# SCH_FINAL-Kickbots-joystick-2026-06-17.net
KiCad netlist of a schematic drawn in EasyEDA
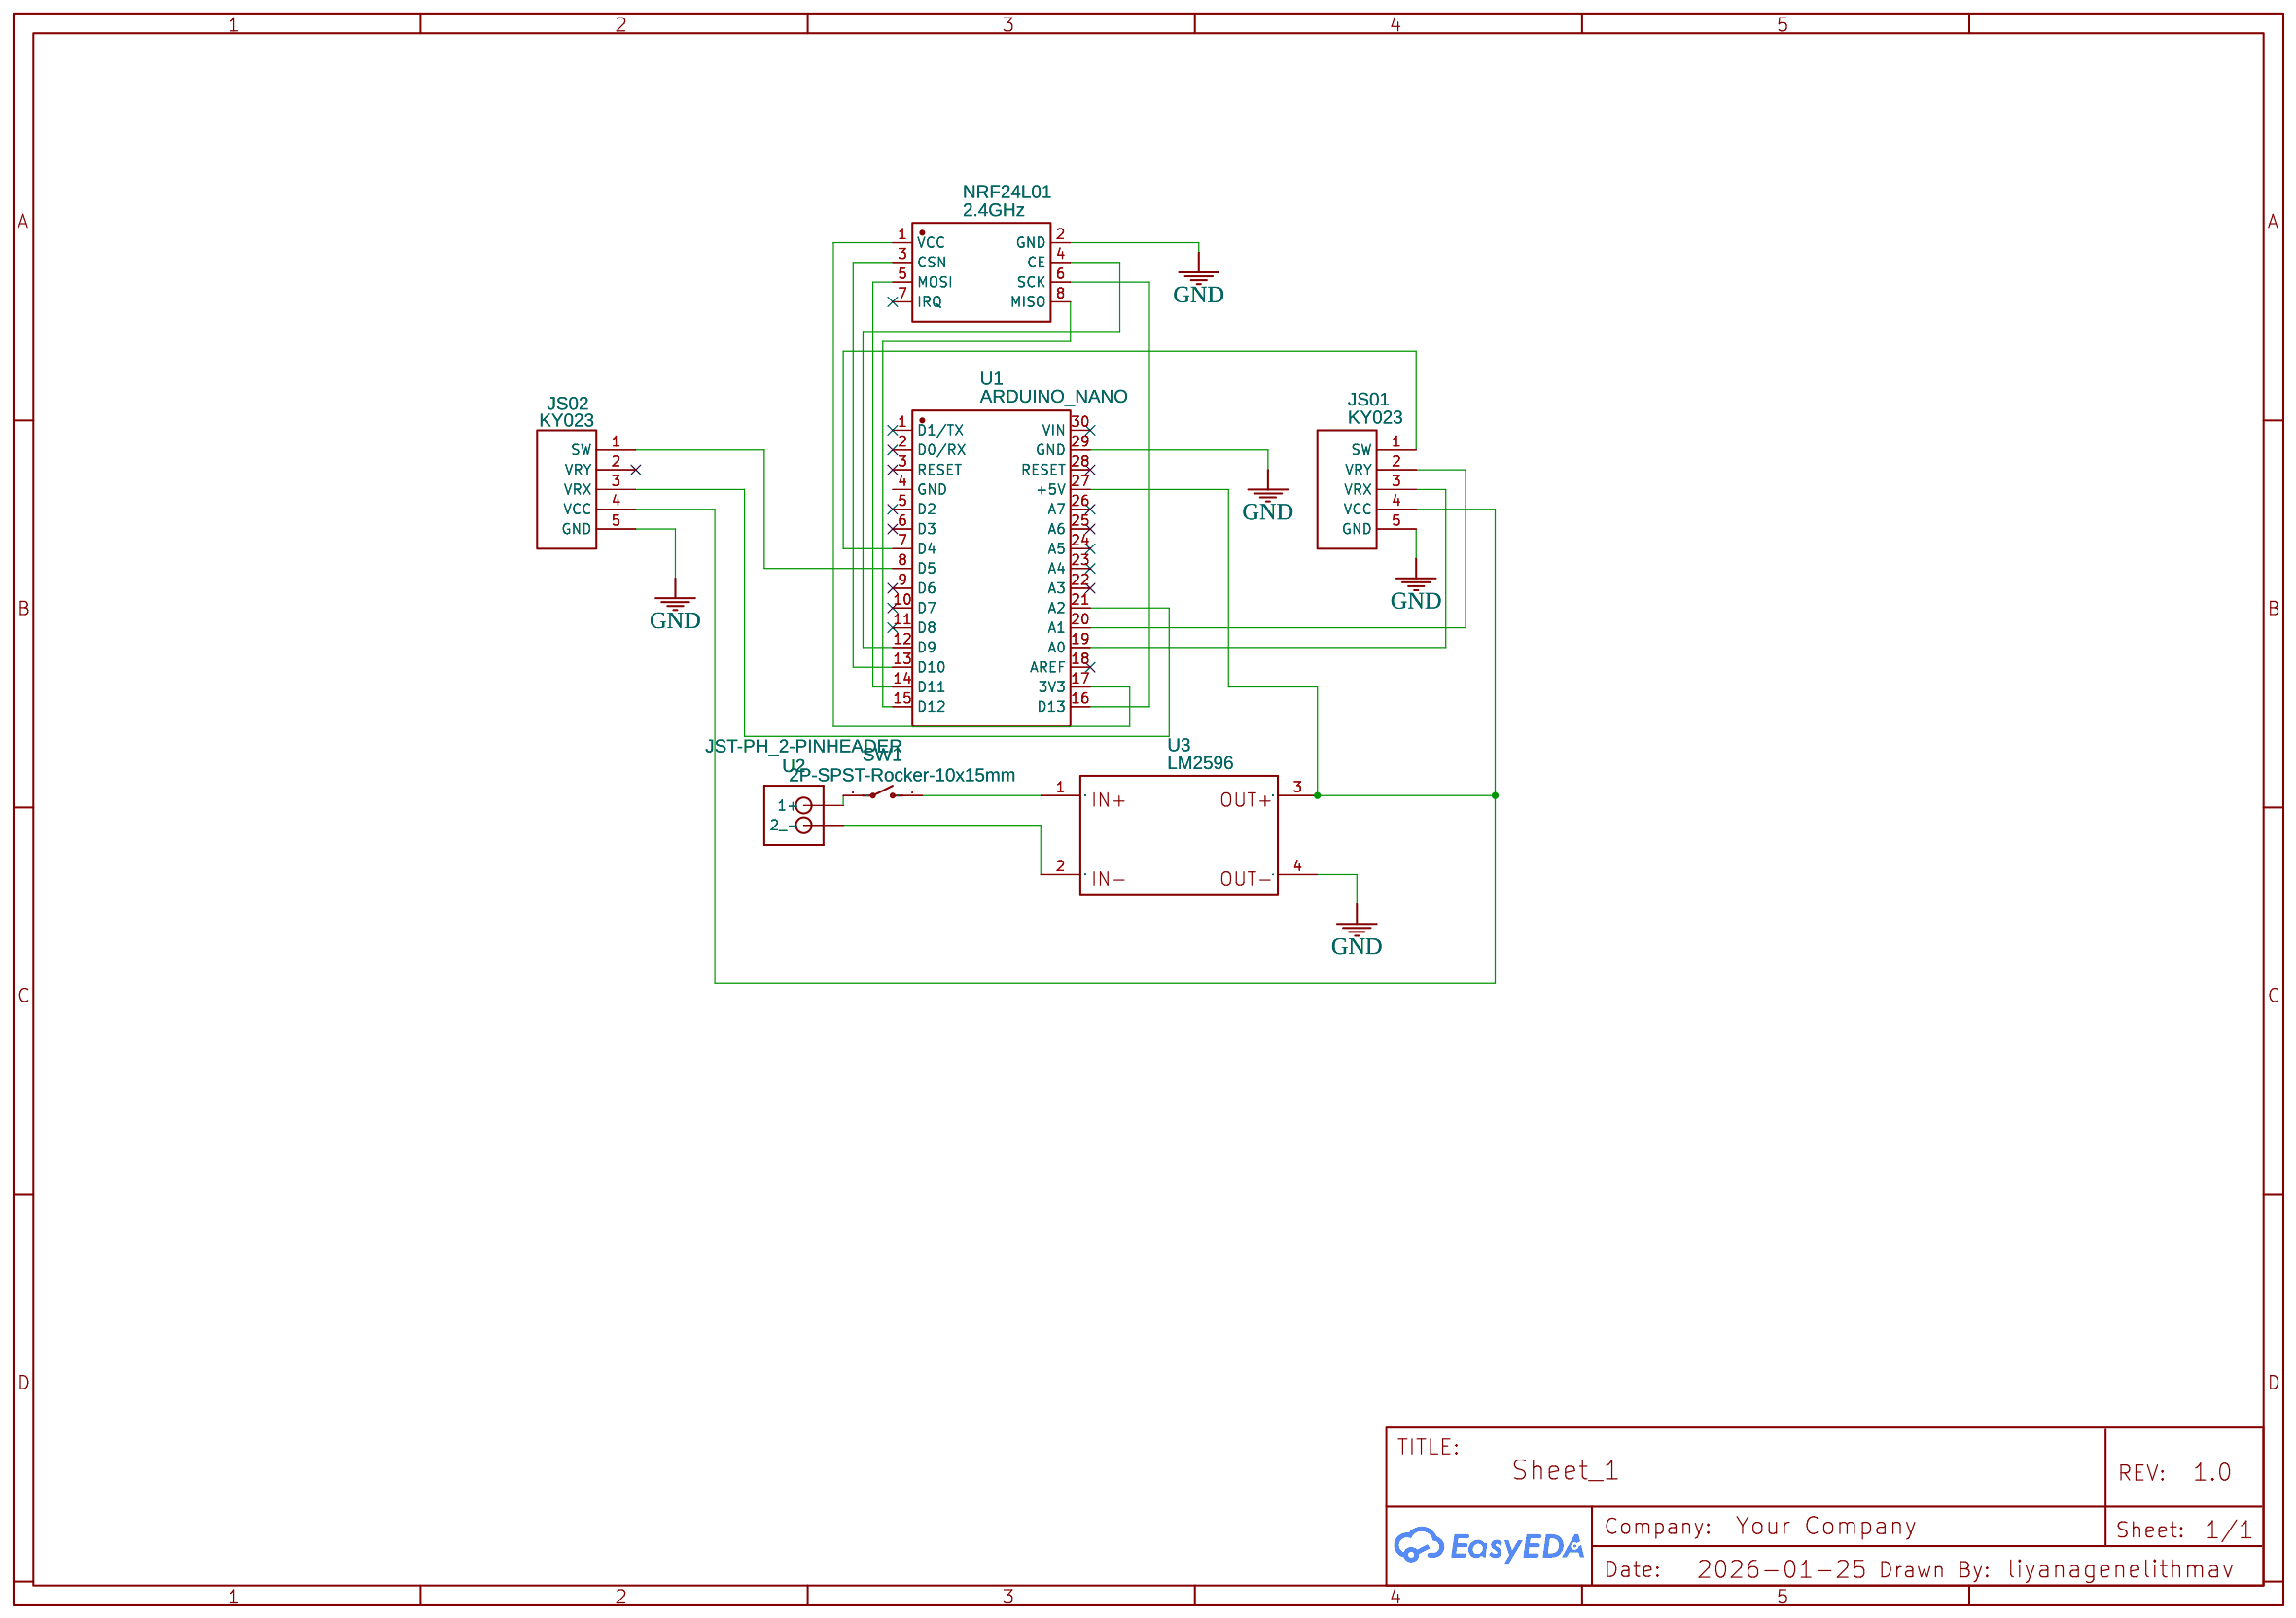
[diagram p0: schematic sheet]

(export (version "E")
  (design (tool "Eeschema 10.0.6"))
  (components
    (comp (ref "JS01") (value "KY023") (libsource (lib "") (part "KY023")))
    (comp (ref "JS02") (value "KY023") (libsource (lib "") (part "KY023")))
    (comp (ref "NRF24L01")
      (value "2.4GHz")
      (fields (field (name "Manufacturer Part") "NF-04") (field (name "Manufacturer") "Ai-Thinker(安信可)"))
      (libsource (lib "") (part "NRF24L01"))
    )
    (comp (ref "SW1")
      (value "2P-SPST-Rocker-10x15mm")
      (fields (field (name "Manufacturer Part") "KCD1-11-1.5x1cm"))
      (libsource (lib "") (part "SWITCH-2P-SPST-Rocker-10x15mm"))
    )
    (comp (ref "U1") (value "ARDUINO_NANO") (libsource (lib "") (part "ARDUINO_NANO")))
    (comp (ref "U2") (value "JST-PH_2-PINHEADER") (libsource (lib "") (part "JST-PH_2-PIN_HEADER")))
    (comp (ref "U3") (value "LM2596") (libsource (lib "") (part "LM2596")))
  )
  (nets
    (net (code "1") (name "GND") (class "Default")
      (node (ref "JS01") (pin "5") (pinfunction "GND_5") (pintype "unspecified"))
      (node (ref "JS02") (pin "5") (pinfunction "GND_5") (pintype "unspecified"))
      (node (ref "NRF24L01") (pin "2") (pinfunction "GND_2") (pintype "unspecified"))
      (node (ref "U1") (pin "29") (pinfunction "GND_29") (pintype "unspecified"))
      (node (ref "U3") (pin "4") (pinfunction "4_4") (pintype "unspecified"))
    )
    (net (code "2") (name "Net-(JS01-SW)") (class "Default")
      (node (ref "JS01") (pin "1") (pinfunction "SW_1") (pintype "unspecified"))
      (node (ref "U1") (pin "7") (pinfunction "D4_7") (pintype "unspecified"))
    )
    (net (code "3") (name "Net-(JS01-VCC)") (class "Default")
      (node (ref "JS01") (pin "4") (pinfunction "VCC_4") (pintype "unspecified"))
      (node (ref "JS02") (pin "4") (pinfunction "VCC_4") (pintype "unspecified"))
      (node (ref "U1") (pin "27") (pinfunction "+5V_27") (pintype "unspecified"))
      (node (ref "U3") (pin "3") (pinfunction "3_3") (pintype "unspecified"))
    )
    (net (code "4") (name "Net-(JS01-VRX)") (class "Default")
      (node (ref "JS01") (pin "3") (pinfunction "VRX_3") (pintype "unspecified"))
      (node (ref "U1") (pin "19") (pinfunction "A0_19") (pintype "unspecified"))
    )
    (net (code "5") (name "Net-(JS01-VRY)") (class "Default")
      (node (ref "JS01") (pin "2") (pinfunction "VRY_2") (pintype "unspecified"))
      (node (ref "U1") (pin "20") (pinfunction "A1_20") (pintype "unspecified"))
    )
    (net (code "6") (name "Net-(JS02-SW)") (class "Default")
      (node (ref "JS02") (pin "1") (pinfunction "SW_1") (pintype "unspecified"))
      (node (ref "U1") (pin "8") (pinfunction "D5_8") (pintype "unspecified"))
    )
    (net (code "7") (name "Net-(JS02-VRX)") (class "Default")
      (node (ref "JS02") (pin "3") (pinfunction "VRX_3") (pintype "unspecified"))
      (node (ref "U1") (pin "21") (pinfunction "A2_21") (pintype "unspecified"))
    )
    (net (code "8") (name "Net-(NRF24L01-CE)") (class "Default")
      (node (ref "NRF24L01") (pin "4") (pinfunction "CE_4") (pintype "unspecified"))
      (node (ref "U1") (pin "12") (pinfunction "D9_12") (pintype "unspecified"))
    )
    (net (code "9") (name "Net-(NRF24L01-CSN)") (class "Default")
      (node (ref "NRF24L01") (pin "3") (pinfunction "CSN_3") (pintype "unspecified"))
      (node (ref "U1") (pin "13") (pinfunction "D10_13") (pintype "unspecified"))
    )
    (net (code "10") (name "Net-(NRF24L01-MISO)") (class "Default")
      (node (ref "NRF24L01") (pin "8") (pinfunction "MISO_8") (pintype "unspecified"))
      (node (ref "U1") (pin "15") (pinfunction "D12_15") (pintype "unspecified"))
    )
    (net (code "11") (name "Net-(NRF24L01-MOSI)") (class "Default")
      (node (ref "NRF24L01") (pin "5") (pinfunction "MOSI_5") (pintype "unspecified"))
      (node (ref "U1") (pin "14") (pinfunction "D11_14") (pintype "unspecified"))
    )
    (net (code "12") (name "Net-(NRF24L01-SCK)") (class "Default")
      (node (ref "NRF24L01") (pin "6") (pinfunction "SCK_6") (pintype "unspecified"))
      (node (ref "U1") (pin "16") (pinfunction "D13_16") (pintype "unspecified"))
    )
    (net (code "13") (name "Net-(NRF24L01-VCC)") (class "Default")
      (node (ref "NRF24L01") (pin "1") (pinfunction "VCC_1") (pintype "unspecified"))
      (node (ref "U1") (pin "17") (pinfunction "3V3_17") (pintype "unspecified"))
    )
    (net (code "14") (name "Net-(SW1-O)") (class "Default")
      (node (ref "SW1") (pin "1") (pinfunction "O_1") (pintype "unspecified"))
      (node (ref "U3") (pin "1") (pinfunction "1_1") (pintype "unspecified"))
    )
    (net (code "15") (name "Net-(SW1-P)") (class "Default")
      (node (ref "SW1") (pin "2") (pinfunction "P_2") (pintype "unspecified"))
      (node (ref "U2") (pin "P1") (pinfunction "1+_P1") (pintype "unspecified"))
    )
    (net (code "16") (name "Net-(U2-2_-)") (class "Default")
      (node (ref "U2") (pin "P2") (pinfunction "2_-_P2") (pintype "unspecified"))
      (node (ref "U3") (pin "2") (pinfunction "2_2") (pintype "unspecified"))
    )
    (net (code "17") (name "unconnected-(JS02-VRY-Pad2)") (class "Default")
      (node (ref "JS02") (pin "2") (pinfunction "VRY_2") (pintype "unspecified+no_connect"))
    )
    (net (code "18") (name "unconnected-(NRF24L01-IRQ-Pad7)") (class "Default")
      (node (ref "NRF24L01") (pin "7") (pinfunction "IRQ_7") (pintype "unspecified+no_connect"))
    )
    (net (code "19") (name "unconnected-(U1-A3-Pad22)") (class "Default")
      (node (ref "U1") (pin "22") (pinfunction "A3_22") (pintype "unspecified+no_connect"))
    )
    (net (code "20") (name "unconnected-(U1-A4-Pad23)") (class "Default")
      (node (ref "U1") (pin "23") (pinfunction "A4_23") (pintype "unspecified+no_connect"))
    )
    (net (code "21") (name "unconnected-(U1-A5-Pad24)") (class "Default")
      (node (ref "U1") (pin "24") (pinfunction "A5_24") (pintype "unspecified+no_connect"))
    )
    (net (code "22") (name "unconnected-(U1-A6-Pad25)") (class "Default")
      (node (ref "U1") (pin "25") (pinfunction "A6_25") (pintype "unspecified+no_connect"))
    )
    (net (code "23") (name "unconnected-(U1-A7-Pad26)") (class "Default")
      (node (ref "U1") (pin "26") (pinfunction "A7_26") (pintype "unspecified+no_connect"))
    )
    (net (code "24") (name "unconnected-(U1-AREF-Pad18)") (class "Default")
      (node (ref "U1") (pin "18") (pinfunction "AREF_18") (pintype "unspecified+no_connect"))
    )
    (net (code "25") (name "unconnected-(U1-D0{slash}RX-Pad2)") (class "Default")
      (node (ref "U1") (pin "2") (pinfunction "D0/RX_2") (pintype "unspecified+no_connect"))
    )
    (net (code "26") (name "unconnected-(U1-D1{slash}TX-Pad1)") (class "Default")
      (node (ref "U1") (pin "1") (pinfunction "D1/TX_1") (pintype "unspecified+no_connect"))
    )
    (net (code "27") (name "unconnected-(U1-D2-Pad5)") (class "Default")
      (node (ref "U1") (pin "5") (pinfunction "D2_5") (pintype "unspecified+no_connect"))
    )
    (net (code "28") (name "unconnected-(U1-D3-Pad6)") (class "Default")
      (node (ref "U1") (pin "6") (pinfunction "D3_6") (pintype "unspecified+no_connect"))
    )
    (net (code "29") (name "unconnected-(U1-D6-Pad9)") (class "Default")
      (node (ref "U1") (pin "9") (pinfunction "D6_9") (pintype "unspecified+no_connect"))
    )
    (net (code "30") (name "unconnected-(U1-D7-Pad10)") (class "Default")
      (node (ref "U1") (pin "10") (pinfunction "D7_10") (pintype "unspecified+no_connect"))
    )
    (net (code "31") (name "unconnected-(U1-D8-Pad11)") (class "Default")
      (node (ref "U1") (pin "11") (pinfunction "D8_11") (pintype "unspecified+no_connect"))
    )
    (net (code "32") (name "unconnected-(U1-GND-Pad4)") (class "Default")
      (node (ref "U1") (pin "4") (pinfunction "GND_4") (pintype "unspecified"))
    )
    (net (code "33") (name "unconnected-(U1-RESET-Pad3)") (class "Default")
      (node (ref "U1") (pin "3") (pinfunction "RESET_3") (pintype "unspecified+no_connect"))
    )
    (net (code "34") (name "unconnected-(U1-RESET-Pad28)") (class "Default")
      (node (ref "U1") (pin "28") (pinfunction "RESET_28") (pintype "unspecified+no_connect"))
    )
    (net (code "35") (name "unconnected-(U1-VIN-Pad30)") (class "Default")
      (node (ref "U1") (pin "30") (pinfunction "VIN_30") (pintype "unspecified+no_connect"))
    )
  )
)
